# q4.net
KiCad netlist of a schematic drawn in EAGLE
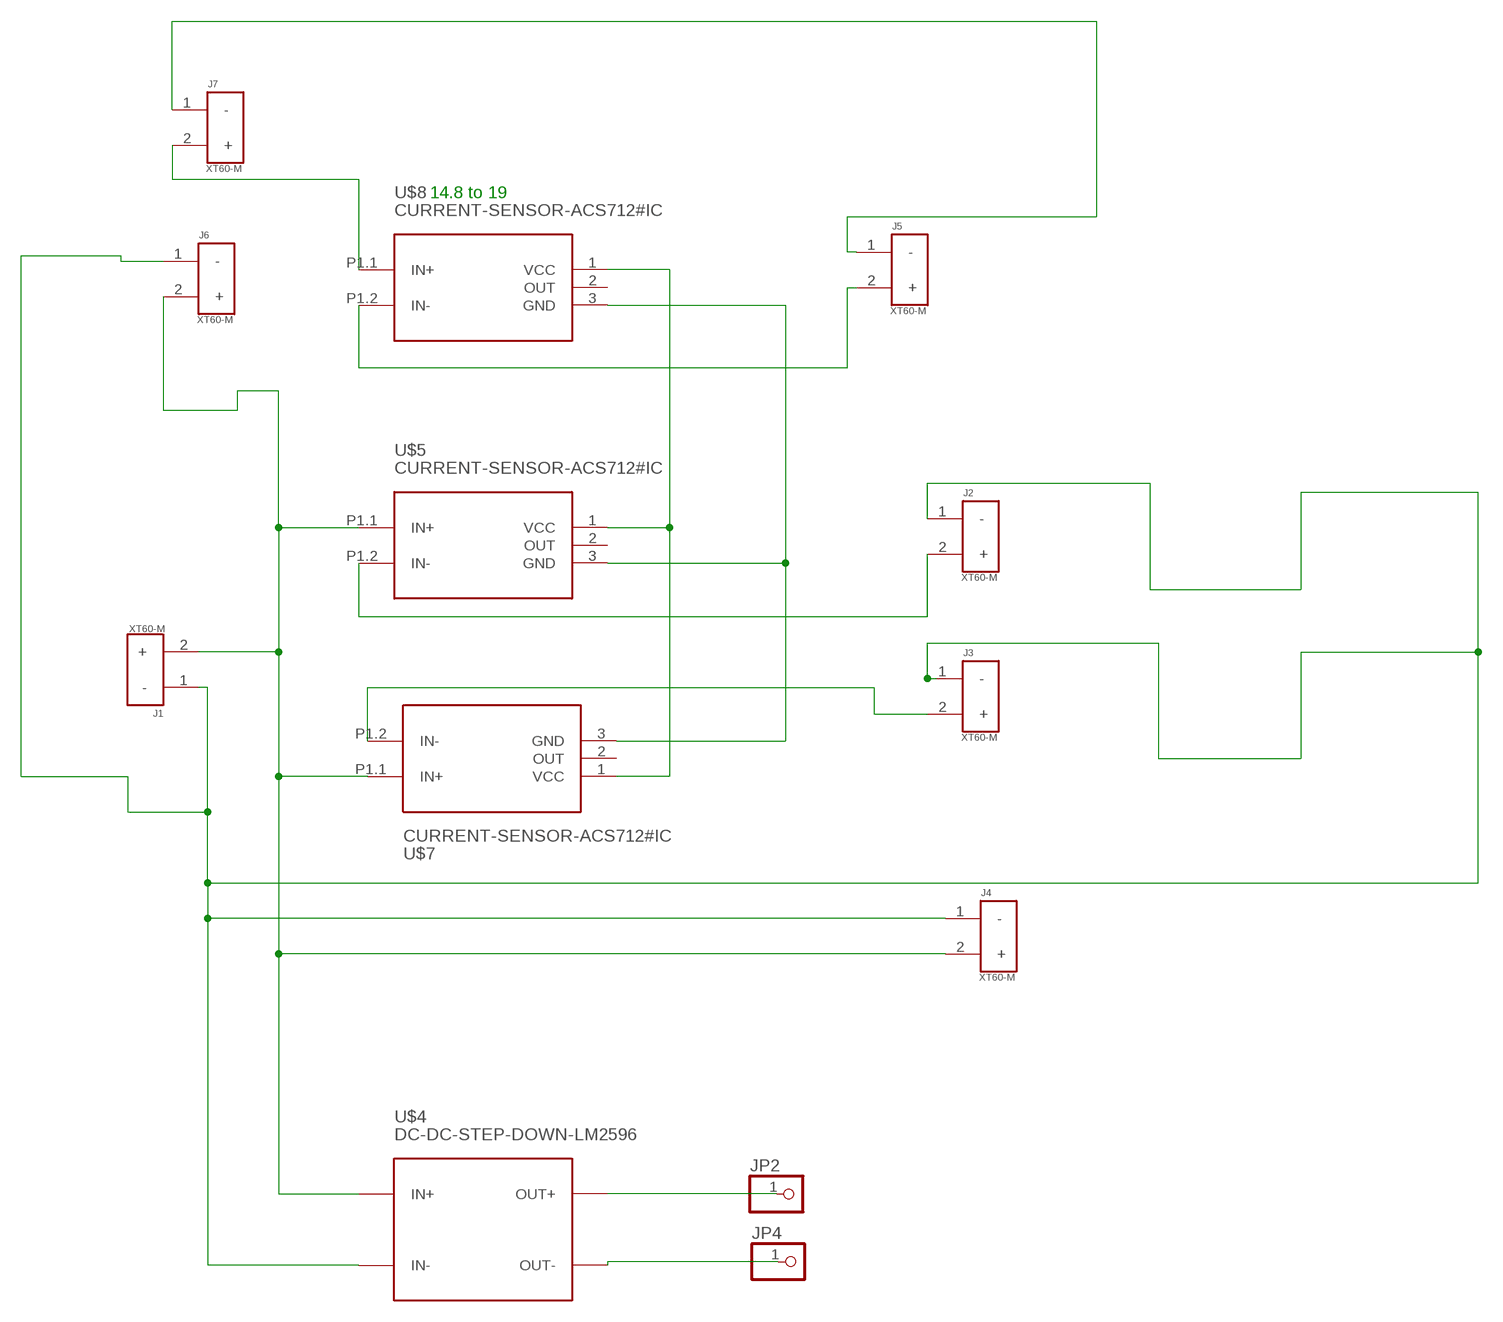
[diagram p0: schematic, sheet 1]

(export (version "E")
  (design (tool "Eeschema 10.0.6"))
  (components
    (comp (ref "J1")
      (value "XT60-M")
      (footprint "eagle-import:AMASS_XT60-M")
      (fields (field (name "MF") "AMASS"))
      (libsource (lib "eagle-import") (part "XT60-M"))
    )
    (comp (ref "J2")
      (value "XT60-M")
      (footprint "eagle-import:AMASS_XT60-M")
      (fields (field (name "MF") "AMASS"))
      (libsource (lib "eagle-import") (part "XT60-M"))
    )
    (comp (ref "J3")
      (value "XT60-M")
      (footprint "eagle-import:AMASS_XT60-M")
      (fields (field (name "MF") "AMASS"))
      (libsource (lib "eagle-import") (part "XT60-M"))
    )
    (comp (ref "J4")
      (value "XT60-M")
      (footprint "eagle-import:AMASS_XT60-M")
      (fields (field (name "MF") "AMASS"))
      (libsource (lib "eagle-import") (part "XT60-M"))
    )
    (comp (ref "J5")
      (value "XT60-M")
      (footprint "eagle-import:AMASS_XT60-M")
      (fields (field (name "MF") "AMASS"))
      (libsource (lib "eagle-import") (part "XT60-M"))
    )
    (comp (ref "J6")
      (value "XT60-M")
      (footprint "eagle-import:AMASS_XT60-M")
      (fields (field (name "MF") "AMASS"))
      (libsource (lib "eagle-import") (part "XT60-M"))
    )
    (comp (ref "J7")
      (value "XT60-M")
      (footprint "eagle-import:AMASS_XT60-M")
      (fields (field (name "MF") "AMASS"))
      (libsource (lib "eagle-import") (part "XT60-M"))
    )
    (comp (ref "JP2")
      (value "PINHD-1X1")
      (footprint "eagle-import:1X01")
      (libsource (lib "eagle-import") (part "PINHD-1X1"))
    )
    (comp (ref "JP4")
      (value "PINHD-1X1")
      (footprint "eagle-import:1X01")
      (libsource (lib "eagle-import") (part "PINHD-1X1"))
    )
    (comp (ref "U$4")
      (value "DC-DC-STEP-DOWN-LM2596")
      (footprint "eagle-import:DC-DC-STEP-DOWN-LM2596")
      (libsource (lib "eagle-import") (part "DC-DC-STEP-DOWN-LM2596"))
    )
    (comp (ref "U$5")
      (value "CURRENT-SENSOR-ACS712#IC")
      (footprint "eagle-import:CURRENT-SENSOR-ACS712#IC")
      (libsource (lib "eagle-import") (part "CURRENT-SENSOR-ACS712#IC"))
    )
    (comp (ref "U$7")
      (value "CURRENT-SENSOR-ACS712#IC")
      (footprint "eagle-import:CURRENT-SENSOR-ACS712#IC")
      (libsource (lib "eagle-import") (part "CURRENT-SENSOR-ACS712#IC"))
    )
    (comp (ref "U$8")
      (value "CURRENT-SENSOR-ACS712#IC")
      (footprint "eagle-import:CURRENT-SENSOR-ACS712#IC")
      (libsource (lib "eagle-import") (part "CURRENT-SENSOR-ACS712#IC"))
    )
  )
  (nets
    (net (code "1") (name "Net-(J1-+)") (class "Default")
      (node (ref "J1") (pin "2") (pinfunction "+_2") (pintype "passive"))
      (node (ref "J4") (pin "2") (pinfunction "+_2") (pintype "passive"))
      (node (ref "J6") (pin "2") (pinfunction "+_2") (pintype "passive"))
      (node (ref "U$4") (pin "IN+") (pinfunction "IN+_IN+") (pintype "bidirectional"))
      (node (ref "U$5") (pin "P1.1") (pinfunction "IN+_P1.1") (pintype "bidirectional"))
      (node (ref "U$7") (pin "P1.1") (pinfunction "IN+_P1.1") (pintype "bidirectional"))
    )
    (net (code "2") (name "Net-(J1--)") (class "Default")
      (node (ref "J1") (pin "1") (pinfunction "-_1") (pintype "passive"))
      (node (ref "J2") (pin "1") (pinfunction "-_1") (pintype "passive"))
      (node (ref "J3") (pin "1") (pinfunction "-_1") (pintype "passive"))
      (node (ref "J4") (pin "1") (pinfunction "-_1") (pintype "passive"))
      (node (ref "J6") (pin "1") (pinfunction "-_1") (pintype "passive"))
      (node (ref "U$4") (pin "IN-") (pinfunction "IN-_IN-") (pintype "bidirectional"))
    )
    (net (code "3") (name "Net-(J2-+)") (class "Default")
      (node (ref "J2") (pin "2") (pinfunction "+_2") (pintype "passive"))
      (node (ref "U$5") (pin "P1.2") (pinfunction "IN-_P1.2") (pintype "bidirectional"))
    )
    (net (code "4") (name "Net-(J3-+)") (class "Default")
      (node (ref "J3") (pin "2") (pinfunction "+_2") (pintype "passive"))
      (node (ref "U$7") (pin "P1.2") (pinfunction "IN-_P1.2") (pintype "bidirectional"))
    )
    (net (code "5") (name "Net-(J5-+)") (class "Default")
      (node (ref "J5") (pin "2") (pinfunction "+_2") (pintype "passive"))
      (node (ref "U$8") (pin "P1.2") (pinfunction "IN-_P1.2") (pintype "bidirectional"))
    )
    (net (code "6") (name "Net-(J5--)") (class "Default")
      (node (ref "J5") (pin "1") (pinfunction "-_1") (pintype "passive"))
      (node (ref "J7") (pin "1") (pinfunction "-_1") (pintype "passive"))
    )
    (net (code "7") (name "Net-(J7-+)") (class "Default")
      (node (ref "J7") (pin "2") (pinfunction "+_2") (pintype "passive"))
      (node (ref "U$8") (pin "P1.1") (pinfunction "IN+_P1.1") (pintype "bidirectional"))
    )
    (net (code "8") (name "Net-(JP2-Pad1)") (class "Default")
      (node (ref "JP2") (pin "1") (pinfunction "1_1") (pintype "passive"))
      (node (ref "U$4") (pin "OUT+") (pinfunction "OUT+_OUT+") (pintype "bidirectional"))
    )
    (net (code "9") (name "Net-(JP4-Pad1)") (class "Default")
      (node (ref "JP4") (pin "1") (pinfunction "1_1") (pintype "passive"))
      (node (ref "U$4") (pin "OUT-") (pinfunction "OUT-_OUT-") (pintype "bidirectional"))
    )
    (net (code "10") (name "Net-(U$5-GND)") (class "Default")
      (node (ref "U$5") (pin "3") (pinfunction "GND_3") (pintype "power_in"))
      (node (ref "U$7") (pin "3") (pinfunction "GND_3") (pintype "power_in"))
      (node (ref "U$8") (pin "3") (pinfunction "GND_3") (pintype "power_in"))
    )
    (net (code "11") (name "Net-(U$5-VCC)") (class "Default")
      (node (ref "U$5") (pin "1") (pinfunction "VCC_1") (pintype "power_in"))
      (node (ref "U$7") (pin "1") (pinfunction "VCC_1") (pintype "power_in"))
      (node (ref "U$8") (pin "1") (pinfunction "VCC_1") (pintype "power_in"))
    )
    (net (code "12") (name "unconnected-(U$5-OUT-Pad2)") (class "Default")
      (node (ref "U$5") (pin "2") (pinfunction "OUT_2") (pintype "output"))
    )
    (net (code "13") (name "unconnected-(U$7-OUT-Pad2)") (class "Default")
      (node (ref "U$7") (pin "2") (pinfunction "OUT_2") (pintype "output"))
    )
    (net (code "14") (name "unconnected-(U$8-OUT-Pad2)") (class "Default")
      (node (ref "U$8") (pin "2") (pinfunction "OUT_2") (pintype "output"))
    )
  )
)
